# cyborg_ring_v0.net
KiCad netlist of a schematic drawn in EAGLE
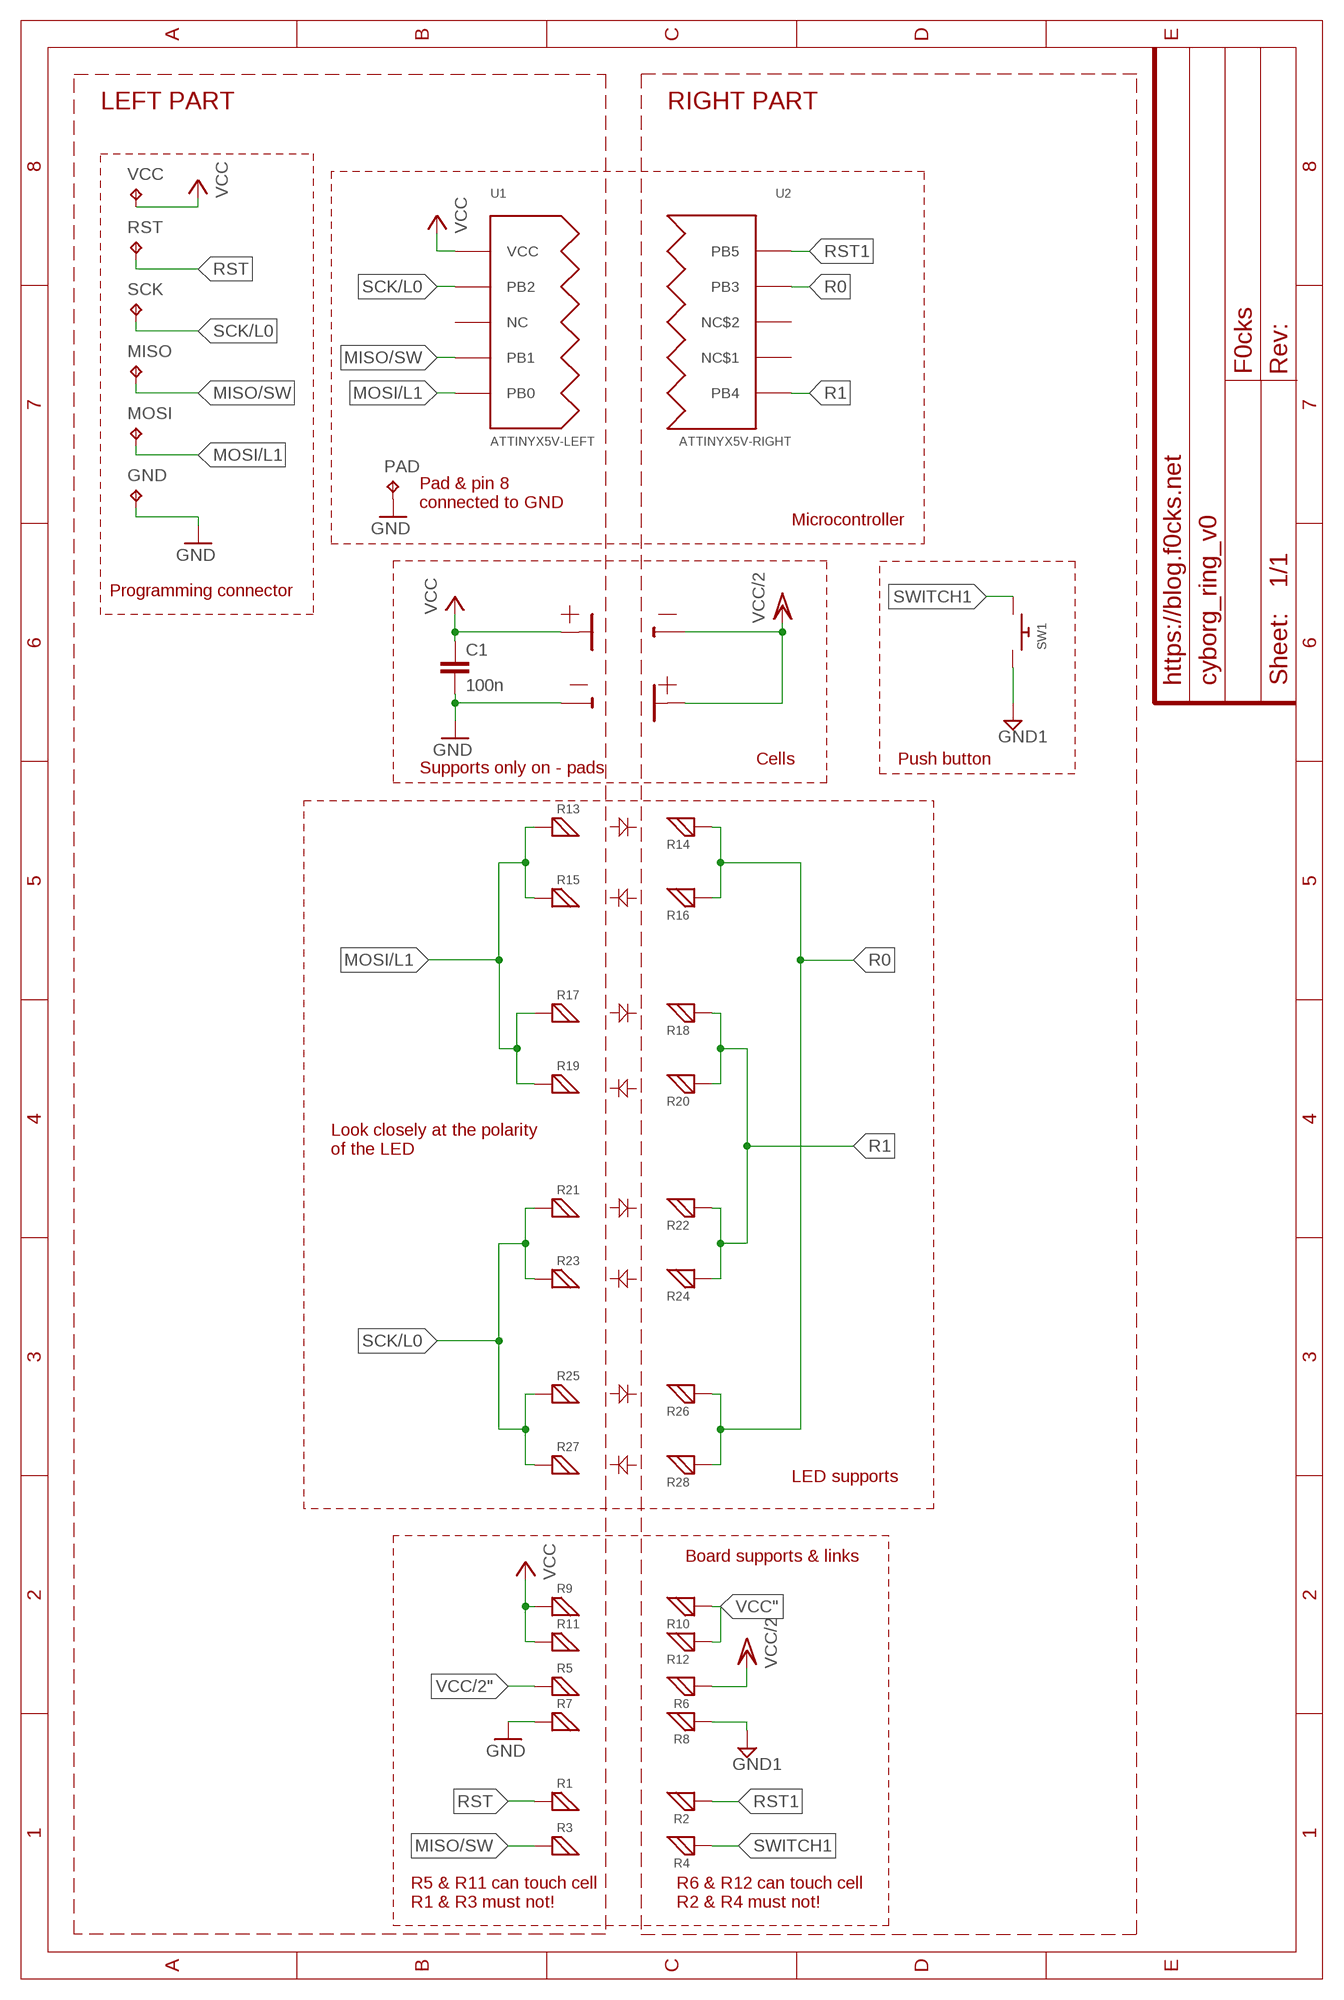
[diagram p0: schematic, sheet 1]

(export (version "E")
  (design (tool "Eeschema 10.0.6"))
  (components
    (comp (ref "C1")
      (value "100n")
      (footprint "eagle-import:C0201")
      (libsource (lib "eagle-import") (part "C-EUC0201"))
    )
    (comp (ref "GND")
      (value "TPTP15R")
      (footprint "eagle-import:TP15R")
      (libsource (lib "eagle-import") (part "TPTP15R"))
    )
    (comp (ref "MISO")
      (value "TPTP15R")
      (footprint "eagle-import:TP15R")
      (libsource (lib "eagle-import") (part "TPTP15R"))
    )
    (comp (ref "MOSI")
      (value "TPTP15R")
      (footprint "eagle-import:TP15R")
      (libsource (lib "eagle-import") (part "TPTP15R"))
    )
    (comp (ref "PAD")
      (value "TPTP06R")
      (footprint "eagle-import:TP06R")
      (libsource (lib "eagle-import") (part "TPTP06R"))
    )
    (comp (ref "R1")
      (value "R0805-1/2TEST")
      (footprint "eagle-import:R0805-1_2")
      (libsource (lib "eagle-import") (part "R0805-1/2TEST"))
    )
    (comp (ref "R2")
      (value "R0805-1/2TEST")
      (footprint "eagle-import:R0805-1_2")
      (libsource (lib "eagle-import") (part "R0805-1/2TEST"))
    )
    (comp (ref "R3")
      (value "R0805-1/2TEST")
      (footprint "eagle-import:R0805-1_2")
      (libsource (lib "eagle-import") (part "R0805-1/2TEST"))
    )
    (comp (ref "R4")
      (value "R0805-1/2TEST")
      (footprint "eagle-import:R0805-1_2")
      (libsource (lib "eagle-import") (part "R0805-1/2TEST"))
    )
    (comp (ref "R5")
      (value "R0805-1/2TEST2")
      (footprint "eagle-import:R0905-1_2BIS")
      (libsource (lib "eagle-import") (part "R0805-1/2TEST2"))
    )
    (comp (ref "R6")
      (value "R0805-1/2TEST2")
      (footprint "eagle-import:R0905-1_2BIS")
      (libsource (lib "eagle-import") (part "R0805-1/2TEST2"))
    )
    (comp (ref "R7")
      (value "R0805-1/2TEST")
      (footprint "eagle-import:R0805-1_2")
      (libsource (lib "eagle-import") (part "R0805-1/2TEST"))
    )
    (comp (ref "R8")
      (value "R0805-1/2TEST")
      (footprint "eagle-import:R0805-1_2")
      (libsource (lib "eagle-import") (part "R0805-1/2TEST"))
    )
    (comp (ref "R9")
      (value "R0805-1/2TEST")
      (footprint "eagle-import:R0805-1_2")
      (libsource (lib "eagle-import") (part "R0805-1/2TEST"))
    )
    (comp (ref "R10")
      (value "R0805-1/2TEST")
      (footprint "eagle-import:R0805-1_2")
      (libsource (lib "eagle-import") (part "R0805-1/2TEST"))
    )
    (comp (ref "R11")
      (value "R0805-1/2TEST2")
      (footprint "eagle-import:R0905-1_2BIS")
      (libsource (lib "eagle-import") (part "R0805-1/2TEST2"))
    )
    (comp (ref "R12")
      (value "R0805-1/2TEST2")
      (footprint "eagle-import:R0905-1_2BIS")
      (libsource (lib "eagle-import") (part "R0805-1/2TEST2"))
    )
    (comp (ref "R13")
      (value "R0508-1/2")
      (footprint "eagle-import:R0508-1_2")
      (libsource (lib "eagle-import") (part "R0508-1/2"))
    )
    (comp (ref "R14")
      (value "R0508-1/2")
      (footprint "eagle-import:R0508-1_2")
      (libsource (lib "eagle-import") (part "R0508-1/2"))
    )
    (comp (ref "R15")
      (value "R0508-1/2")
      (footprint "eagle-import:R0508-1_2")
      (libsource (lib "eagle-import") (part "R0508-1/2"))
    )
    (comp (ref "R16")
      (value "R0508-1/2")
      (footprint "eagle-import:R0508-1_2")
      (libsource (lib "eagle-import") (part "R0508-1/2"))
    )
    (comp (ref "R17")
      (value "R0508-1/2")
      (footprint "eagle-import:R0508-1_2")
      (libsource (lib "eagle-import") (part "R0508-1/2"))
    )
    (comp (ref "R18")
      (value "R0508-1/2")
      (footprint "eagle-import:R0508-1_2")
      (libsource (lib "eagle-import") (part "R0508-1/2"))
    )
    (comp (ref "R19")
      (value "R0508-1/2")
      (footprint "eagle-import:R0508-1_2")
      (libsource (lib "eagle-import") (part "R0508-1/2"))
    )
    (comp (ref "R20")
      (value "R0508-1/2")
      (footprint "eagle-import:R0508-1_2")
      (libsource (lib "eagle-import") (part "R0508-1/2"))
    )
    (comp (ref "R21")
      (value "R0508-1/2")
      (footprint "eagle-import:R0508-1_2")
      (libsource (lib "eagle-import") (part "R0508-1/2"))
    )
    (comp (ref "R22")
      (value "R0508-1/2")
      (footprint "eagle-import:R0508-1_2")
      (libsource (lib "eagle-import") (part "R0508-1/2"))
    )
    (comp (ref "R23")
      (value "R0508-1/2")
      (footprint "eagle-import:R0508-1_2")
      (libsource (lib "eagle-import") (part "R0508-1/2"))
    )
    (comp (ref "R24")
      (value "R0508-1/2")
      (footprint "eagle-import:R0508-1_2")
      (libsource (lib "eagle-import") (part "R0508-1/2"))
    )
    (comp (ref "R25")
      (value "R0508-1/2")
      (footprint "eagle-import:R0508-1_2")
      (libsource (lib "eagle-import") (part "R0508-1/2"))
    )
    (comp (ref "R26")
      (value "R0508-1/2")
      (footprint "eagle-import:R0508-1_2")
      (libsource (lib "eagle-import") (part "R0508-1/2"))
    )
    (comp (ref "R27")
      (value "R0508-1/2")
      (footprint "eagle-import:R0508-1_2")
      (libsource (lib "eagle-import") (part "R0508-1/2"))
    )
    (comp (ref "R28")
      (value "R0508-1/2")
      (footprint "eagle-import:R0508-1_2")
      (libsource (lib "eagle-import") (part "R0508-1/2"))
    )
    (comp (ref "RST")
      (value "TPTP15R")
      (footprint "eagle-import:TP15R")
      (libsource (lib "eagle-import") (part "TPTP15R"))
    )
    (comp (ref "SCK")
      (value "TPTP15R")
      (footprint "eagle-import:TP15R")
      (libsource (lib "eagle-import") (part "TPTP15R"))
    )
    (comp (ref "SW1")
      (value "SWITCH_PUSHBUTTONC&K_KSS")
      (footprint "eagle-import:BTN_CK_KSS")
      (libsource (lib "eagle-import") (part "SWITCH_PUSHBUTTONC&K_KSS"))
    )
    (comp (ref "U$1")
      (value "BAT+")
      (footprint "eagle-import:BAT+")
      (libsource (lib "eagle-import") (part "BAT+"))
    )
    (comp (ref "U$2")
      (value "BAT+")
      (footprint "eagle-import:BAT+")
      (libsource (lib "eagle-import") (part "BAT+"))
    )
    (comp (ref "U$3")
      (value "BAT-")
      (footprint "eagle-import:BAT-")
      (libsource (lib "eagle-import") (part "BAT-"))
    )
    (comp (ref "U$4")
      (value "BAT-")
      (footprint "eagle-import:BAT-")
      (libsource (lib "eagle-import") (part "BAT-"))
    )
    (comp (ref "U1")
      (value "ATTINYX5V-LEFT")
      (footprint "eagle-import:1_4-QFN20")
      (libsource (lib "eagle-import") (part "ATTINYX5V-LEFT"))
    )
    (comp (ref "U2")
      (value "ATTINYX5V-RIGHT")
      (footprint "eagle-import:1_4-QFN20")
      (libsource (lib "eagle-import") (part "ATTINYX5V-RIGHT"))
    )
    (comp (ref "VCC")
      (value "TPTP15R")
      (footprint "eagle-import:TP15R")
      (libsource (lib "eagle-import") (part "TPTP15R"))
    )
  )
  (nets
    (net (code "1") (name "GND") (class "Default")
      (node (ref "C1") (pin "2") (pinfunction "2_2") (pintype "passive"))
      (node (ref "GND") (pin "TP") (pinfunction "TP_TP") (pintype "input"))
      (node (ref "PAD") (pin "TP") (pinfunction "TP_TP") (pintype "input"))
      (node (ref "R7") (pin "1") (pinfunction "P$1_1") (pintype "bidirectional"))
      (node (ref "U$4") (pin "P$1") (pinfunction "-_P$1") (pintype "passive"))
    )
    (net (code "2") (name "GND1") (class "Default")
      (node (ref "R8") (pin "1") (pinfunction "P$1_1") (pintype "bidirectional"))
      (node (ref "SW1") (pin "P$1") (pinfunction "P$1_P$1") (pintype "passive"))
    )
    (net (code "3") (name "MISO{slash}SW") (class "Default")
      (node (ref "MISO") (pin "TP") (pinfunction "TP_TP") (pintype "input"))
      (node (ref "R3") (pin "1") (pinfunction "P$1_1") (pintype "bidirectional"))
      (node (ref "U1") (pin "4") (pinfunction "PB1_4") (pintype "bidirectional"))
    )
    (net (code "4") (name "MOSI{slash}L1") (class "Default")
      (node (ref "MOSI") (pin "TP") (pinfunction "TP_TP") (pintype "input"))
      (node (ref "R13") (pin "P$1") (pinfunction "P$1_P$1") (pintype "bidirectional"))
      (node (ref "R15") (pin "P$1") (pinfunction "P$1_P$1") (pintype "bidirectional"))
      (node (ref "R17") (pin "P$1") (pinfunction "P$1_P$1") (pintype "bidirectional"))
      (node (ref "R19") (pin "P$1") (pinfunction "P$1_P$1") (pintype "bidirectional"))
      (node (ref "U1") (pin "5") (pinfunction "PB0_5") (pintype "bidirectional"))
    )
    (net (code "5") (name "R0") (class "Default")
      (node (ref "R14") (pin "P$1") (pinfunction "P$1_P$1") (pintype "bidirectional"))
      (node (ref "R16") (pin "P$1") (pinfunction "P$1_P$1") (pintype "bidirectional"))
      (node (ref "R26") (pin "P$1") (pinfunction "P$1_P$1") (pintype "bidirectional"))
      (node (ref "R28") (pin "P$1") (pinfunction "P$1_P$1") (pintype "bidirectional"))
      (node (ref "U2") (pin "4") (pinfunction "PB3_4") (pintype "bidirectional"))
    )
    (net (code "6") (name "R1") (class "Default")
      (node (ref "R18") (pin "P$1") (pinfunction "P$1_P$1") (pintype "bidirectional"))
      (node (ref "R20") (pin "P$1") (pinfunction "P$1_P$1") (pintype "bidirectional"))
      (node (ref "R22") (pin "P$1") (pinfunction "P$1_P$1") (pintype "bidirectional"))
      (node (ref "R24") (pin "P$1") (pinfunction "P$1_P$1") (pintype "bidirectional"))
      (node (ref "U2") (pin "1") (pinfunction "PB4_1") (pintype "bidirectional"))
    )
    (net (code "7") (name "RST") (class "Default")
      (node (ref "R1") (pin "1") (pinfunction "P$1_1") (pintype "bidirectional"))
      (node (ref "RST") (pin "TP") (pinfunction "TP_TP") (pintype "input"))
    )
    (net (code "8") (name "RST1") (class "Default")
      (node (ref "R2") (pin "1") (pinfunction "P$1_1") (pintype "bidirectional"))
      (node (ref "U2") (pin "5") (pinfunction "PB5_5") (pintype "bidirectional"))
    )
    (net (code "9") (name "SCK{slash}L0") (class "Default")
      (node (ref "R21") (pin "P$1") (pinfunction "P$1_P$1") (pintype "bidirectional"))
      (node (ref "R23") (pin "P$1") (pinfunction "P$1_P$1") (pintype "bidirectional"))
      (node (ref "R25") (pin "P$1") (pinfunction "P$1_P$1") (pintype "bidirectional"))
      (node (ref "R27") (pin "P$1") (pinfunction "P$1_P$1") (pintype "bidirectional"))
      (node (ref "SCK") (pin "TP") (pinfunction "TP_TP") (pintype "input"))
      (node (ref "U1") (pin "2") (pinfunction "PB2_2") (pintype "bidirectional"))
    )
    (net (code "10") (name "SWITCH1") (class "Default")
      (node (ref "R4") (pin "1") (pinfunction "P$1_1") (pintype "bidirectional"))
      (node (ref "SW1") (pin "P$2") (pinfunction "P$2_P$2") (pintype "passive"))
    )
    (net (code "11") (name "VCC") (class "Default")
      (node (ref "C1") (pin "1") (pinfunction "1_1") (pintype "passive"))
      (node (ref "R11") (pin "1") (pinfunction "P$1_1") (pintype "bidirectional"))
      (node (ref "R9") (pin "1") (pinfunction "P$1_1") (pintype "bidirectional"))
      (node (ref "U$1") (pin "P$1") (pinfunction "+_P$1") (pintype "passive"))
      (node (ref "U1") (pin "1") (pinfunction "VCC_1") (pintype "power_in"))
      (node (ref "VCC") (pin "TP") (pinfunction "TP_TP") (pintype "input"))
    )
    (net (code "12") (name "VCC\"") (class "Default")
      (node (ref "R10") (pin "1") (pinfunction "P$1_1") (pintype "bidirectional"))
      (node (ref "R12") (pin "1") (pinfunction "P$1_1") (pintype "bidirectional"))
    )
    (net (code "13") (name "VCC{slash}2") (class "Default")
      (node (ref "R6") (pin "1") (pinfunction "P$1_1") (pintype "bidirectional"))
      (node (ref "U$2") (pin "P$1") (pinfunction "+_P$1") (pintype "passive"))
      (node (ref "U$3") (pin "P$1") (pinfunction "-_P$1") (pintype "passive"))
    )
    (net (code "14") (name "VCC{slash}2\"") (class "Default")
      (node (ref "R5") (pin "1") (pinfunction "P$1_1") (pintype "bidirectional"))
    )
    (net (code "15") (name "unconnected-(U1-NC-Pad3)") (class "Default")
      (node (ref "U1") (pin "3") (pinfunction "NC_3") (pintype "no_connect"))
    )
    (net (code "16") (name "unconnected-(U2-NC$1-Pad2)") (class "Default")
      (node (ref "U2") (pin "2") (pinfunction "NC$1_2") (pintype "no_connect"))
    )
    (net (code "17") (name "unconnected-(U2-NC$2-Pad3)") (class "Default")
      (node (ref "U2") (pin "3") (pinfunction "NC$2_3") (pintype "no_connect"))
    )
  )
)
